# CY7USB3014.net
KiCad netlist of a schematic drawn in Altium Designer
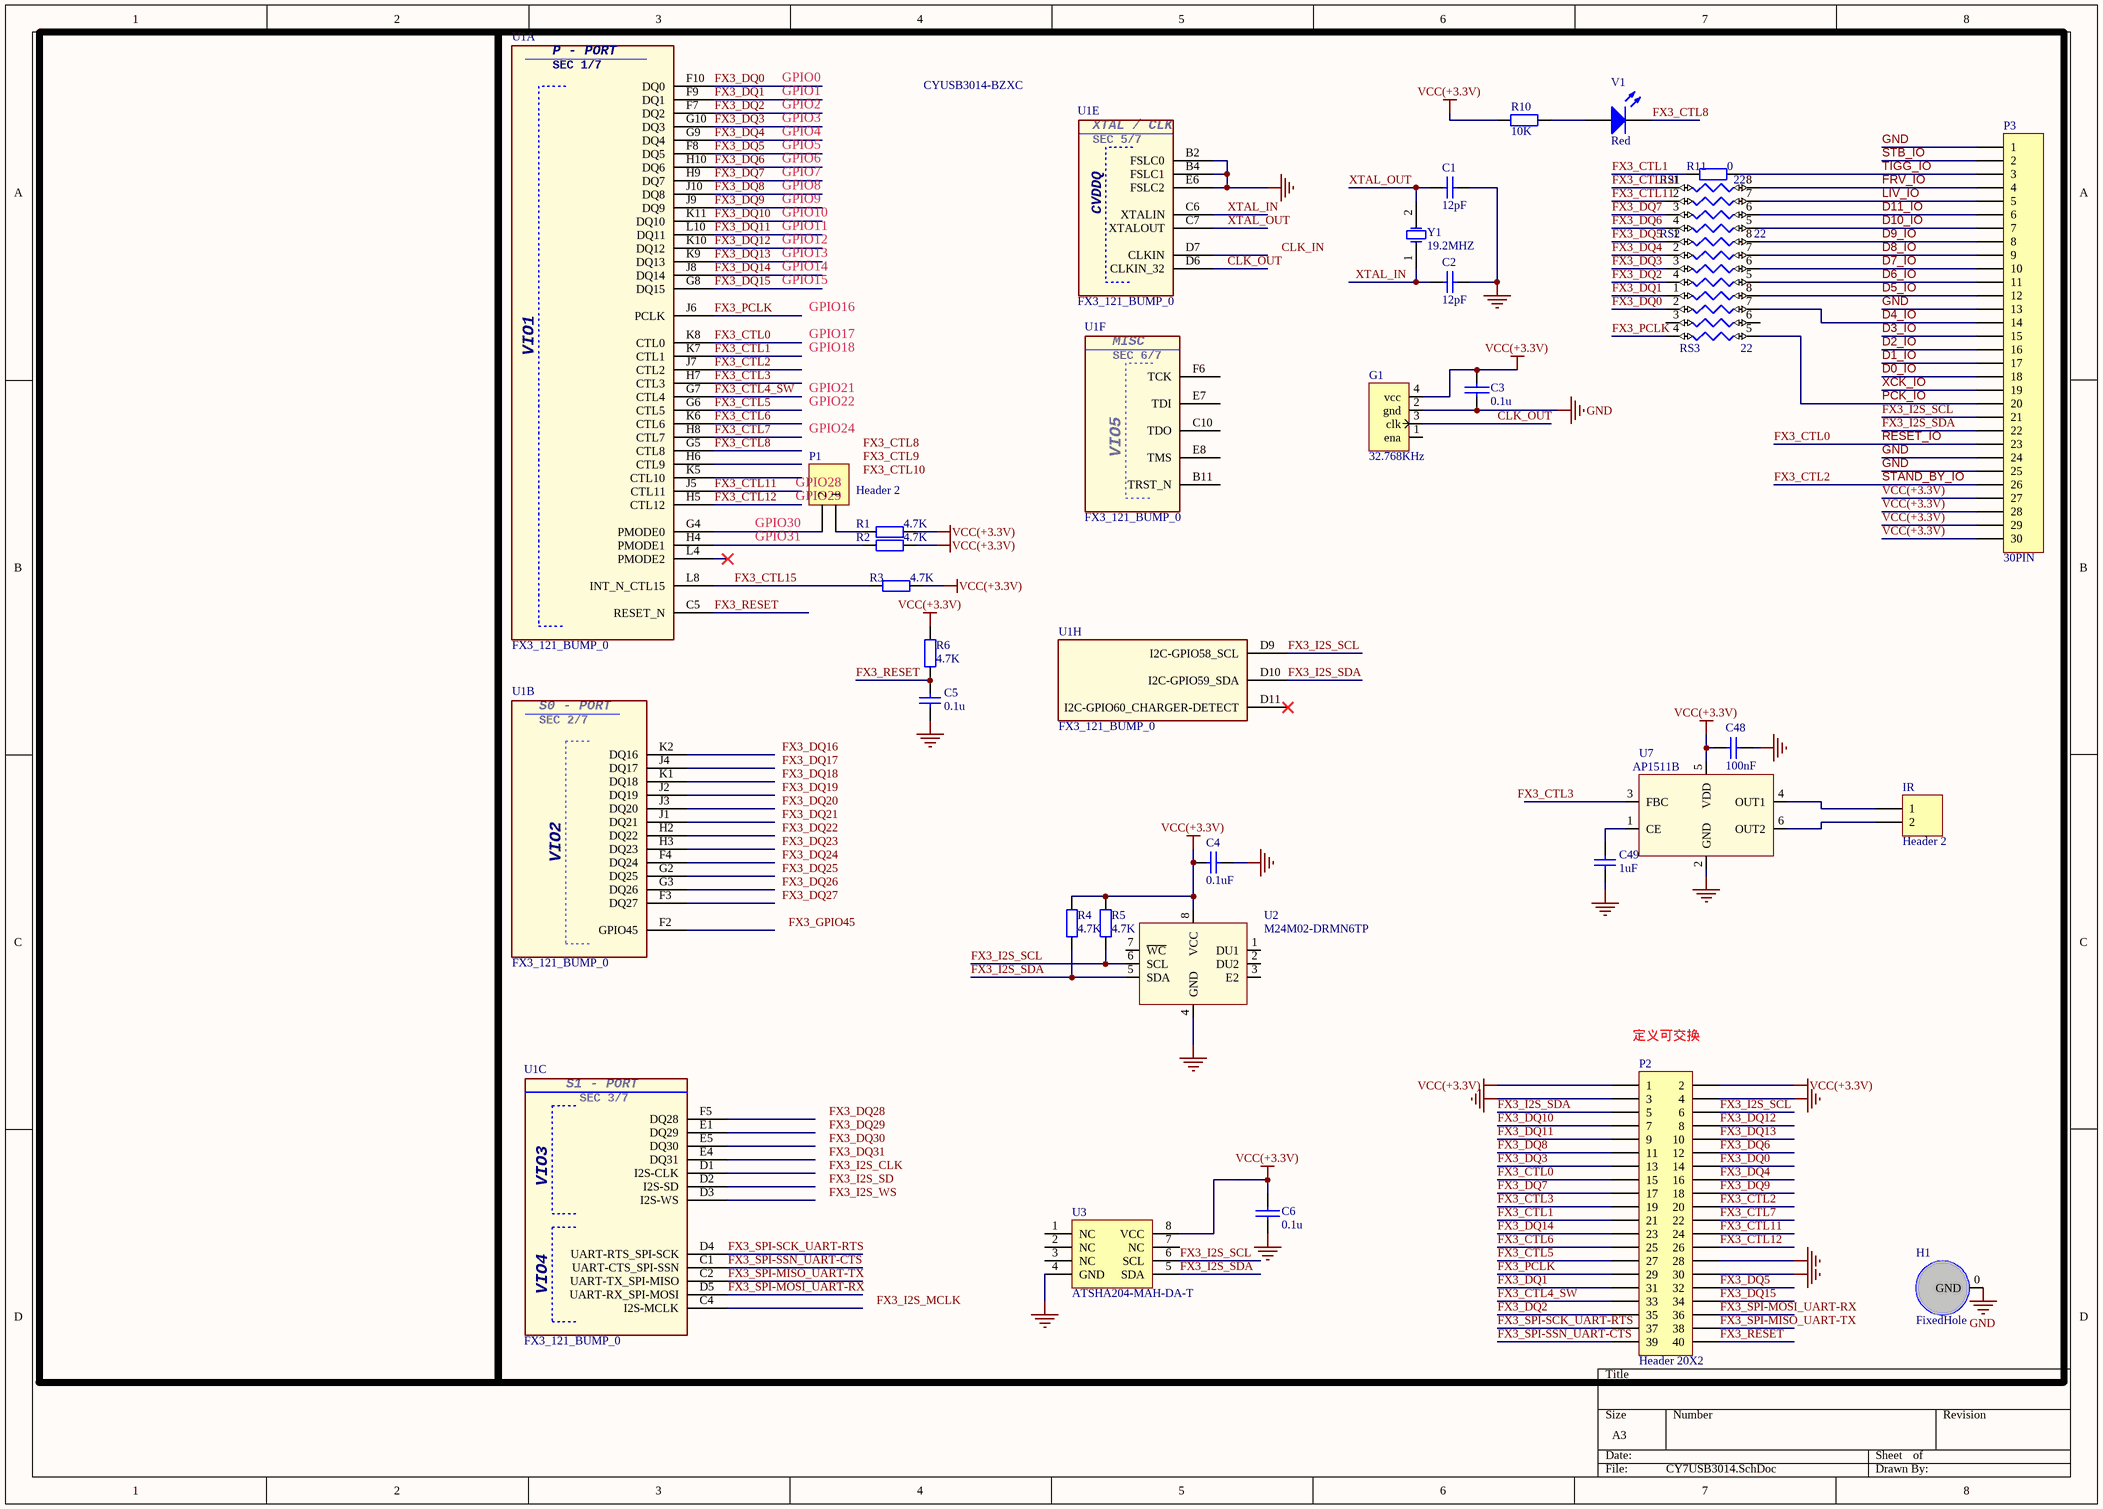
[diagram p0: CY7USB3014.SchDoc]

(export (version "E")
  (design (tool "Eeschema 10.0.6"))
  (components
    (comp (ref "C1")
      (value "12pF")
      (footprint "0603S-CAP")
      (description "CAP CER SMT 4.3pF 0805")
      (fields
        (field (name "2. MANUFACTURERE PART NUMBER") "C0805C439D5GACTU")
        (field (name "8. ALTERNATE PART") "any")
      )
      (libsource (lib "Peeple_eval") (part "CAP CER SMT 4.3pF 0805"))
    )
    (comp (ref "C2")
      (value "12pF")
      (footprint "0603S-CAP")
      (description "CAP CER SMT 4.3pF 0805")
      (fields
        (field (name "2. MANUFACTURERE PART NUMBER") "C0805C439D5GACTU")
        (field (name "8. ALTERNATE PART") "any")
      )
      (libsource (lib "Peeple_eval") (part "CAP CER SMT 4.3pF 0805"))
    )
    (comp (ref "C3")
      (value "0.1u")
      (footprint "0603S-CAP")
      (description "RC=1206")
      (libsource (lib "*") (part "CAP"))
    )
    (comp (ref "C4")
      (value "0.1uF")
      (footprint "0603S-CAP")
      (description "CAP SMT 0.1uF 16V X7R")
      (fields
        (field (name "2. MANUFACTURERE PART NUMBER") "C0805C104K4RACTU")
        (field (name "8. ALTERNATE PART") "any")
      )
      (libsource (lib "Peeple_eval") (part "CAP SMT 0.1uF 16V X7R"))
    )
    (comp (ref "C5")
      (value "0.1u")
      (footprint "0603S-CAP")
      (description "50V/8.2u/0805")
      (fields (field (name "PUBLISHER") "Altium Limited"))
      (libsource (lib "Miscellaneous Devices") (part "Cap"))
    )
    (comp (ref "C6")
      (value "0.1u")
      (footprint "0603S-CAP")
      (description "RC=1206")
      (libsource (lib "*") (part "CAP"))
    )
    (comp (ref "C48")
      (value "100nF")
      (footprint "0603S-CAP")
      (description "50V/8.2u/0805")
      (fields (field (name "PUBLISHER") "Altium Limited"))
      (libsource (lib "Miscellaneous Devices") (part "Cap"))
    )
    (comp (ref "C49")
      (value "1uF")
      (footprint "0603S-CAP")
      (description "50V/8.2u/0805")
      (fields (field (name "PUBLISHER") "Altium Limited"))
      (libsource (lib "Miscellaneous Devices") (part "Cap"))
    )
    (comp (ref "G1") (value "32.768KHz") (footprint "爱普生晶振3.2×2.5mm") (libsource (lib "*") (part "CTY4-B")))
    (comp (ref "H1") (value "FixedHole") (footprint "固定孔_1") (libsource (lib "ITMS-02调试电缆转接板") (part "固定孔")))
    (comp (ref "IR")
      (value "Header 2")
      (footprint "1.25mm")
      (description "Header, 2-Pin")
      (fields (field (name "PUBLISHER") "Altium Limited"))
      (libsource (lib "Miscellaneous Connectors") (part "Header 2"))
    )
    (comp (ref "P1")
      (value "Header 2")
      (footprint "HDR1X2")
      (description "Header, 2-Pin")
      (fields (field (name "PUBLISHER") "Altium Limited"))
      (libsource (lib "") (part "Header 2_1"))
    )
    (comp (ref "P2")
      (value "Header 20X2")
      (footprint "1.27mm 2*20")
      (description "Header, 20-Pin, Dual row")
      (fields (field (name "PUBLISHER") "Altium Limited"))
      (libsource (lib "Miscellaneous Connectors") (part "Header 20X2"))
    )
    (comp (ref "P3")
      (value "30PIN")
      (footprint "FH12-30S-0.5SH")
      (description "Header, 30-Pin")
      (fields (field (name "PUBLISHER") "Altium Limited"))
      (libsource (lib "Miscellaneous Connectors") (part "Header 30"))
    )
    (comp (ref "R1")
      (value "4.7K")
      (footprint "0603S-RES")
      (description "Resistor")
      (fields (field (name "PUBLISHER") "Altium Limited"))
      (libsource (lib "DM642") (part "Res2"))
    )
    (comp (ref "R2")
      (value "4.7K")
      (footprint "0603S-RES")
      (description "Resistor")
      (fields (field (name "PUBLISHER") "Altium Limited"))
      (libsource (lib "DM642") (part "Res2"))
    )
    (comp (ref "R3")
      (value "4.7K")
      (footprint "0603S-RES")
      (description "Resistor")
      (fields (field (name "PUBLISHER") "Altium Limited"))
      (libsource (lib "") (part "Res2_2"))
    )
    (comp (ref "R4")
      (value "4.7K")
      (footprint "0603S-RES")
      (description "Resistor")
      (fields (field (name "PUBLISHER") "Altium Limited"))
      (libsource (lib "DM642") (part "Res2"))
    )
    (comp (ref "R5")
      (value "4.7K")
      (footprint "0603S-RES")
      (description "Resistor")
      (fields (field (name "PUBLISHER") "Altium Limited"))
      (libsource (lib "DM642") (part "Res2"))
    )
    (comp (ref "R6")
      (value "4.7K")
      (footprint "0603S-RES")
      (description "Resistor")
      (fields (field (name "PUBLISHER") "Altium Limited"))
      (libsource (lib "") (part "Res2_3"))
    )
    (comp (ref "R10")
      (value "10K")
      (footprint "0603S-RES")
      (description "Resistor")
      (fields (field (name "PUBLISHER") "Altium Limited"))
      (libsource (lib "") (part "Res2_1"))
    )
    (comp (ref "R11")
      (value "0")
      (footprint "0603S-RES")
      (description "Resistor")
      (fields (field (name "PUBLISHER") "Altium Limited"))
      (libsource (lib "") (part "Res2_1"))
    )
    (comp (ref "RS1") (value "22") (footprint "NC06-4") (libsource (lib "*") (part "RN4")))
    (comp (ref "RS2") (value "22") (footprint "NC06-4") (libsource (lib "*") (part "RN4")))
    (comp (ref "RS3") (value "22") (footprint "NC06-4") (libsource (lib "*") (part "RN4")))
    (comp (ref "U1")
      (value "FX3_121_BUMP_0")
      (footprint "121_BGA_FX3")
      (libsource (lib "USB_CAMERA") (part "FX3_121_BUMP_0"))
    )
    (comp (ref "U2")
      (value "M24M02-DRMN6TP")
      (footprint "SOIC127P600X175-8N")
      (description "IC EEPROM 64KBIT 400KHZ 8SOIC")
      (fields
        (field (name "MANUFACTURER") "Microchip Technology")
        (field (name "MANUFACTURER PART NUMBER") "24LC64-I/SN")
      )
      (libsource (lib "Schlib1") (part "24LC64-I/SN"))
    )
    (comp (ref "U3")
      (value "ATSHA204-MAH-DA-T")
      (footprint "UDFN")
      (libsource (lib "CY7C68013-56") (part "AT24C128"))
    )
    (comp (ref "U7") (value "AP1511B") (footprint "SOT-26") (libsource (lib "noir") (part "AP1511B")))
    (comp (ref "V1")
      (value "Red")
      (footprint "LED0805S")
      (description "Typical INFRARED GaAs LED")
      (fields (field (name "PUBLISHER") "Altium Limited"))
      (libsource (lib "DM642") (part "LED0"))
    )
    (comp (ref "Y1")
      (value "19.2MHZ")
      (footprint "爱普生晶振3.2×2.5MM - 无源")
      (description "Crystal, CRYSTAL 32.768KHZ 6PF SMD")
      (fields
        (field (name "2. MANUFACTURERE PART NUMBER") "ABS07-120-32.768KHZ-T")
        (field (name "4. SUPPLIER PART NUMBER") "535-11937-1-ND")
      )
      (libsource (lib "Peeple_eval") (part "XTAL 32.768KHZ"))
    )
  )
  (nets
    (net (code "2") (name "/CLK_OUT") (class "Default")
      (node (ref "G1") (pin "3") (pinfunction "clk_3") (pintype "passive"))
      (node (ref "U1") (pin "D6") (pinfunction "CLKIN_32_D6") (pintype "passive"))
    )
    (net (code "3") (name "/D0_IO") (class "Default")
      (node (ref "P3") (pin "18") (pinfunction "18_18") (pintype "passive"))
    )
    (net (code "4") (name "/D1_IO") (class "Default")
      (node (ref "P3") (pin "17") (pinfunction "17_17") (pintype "passive"))
    )
    (net (code "5") (name "/D2_IO") (class "Default")
      (node (ref "P3") (pin "16") (pinfunction "16_16") (pintype "passive"))
    )
    (net (code "6") (name "/D3_IO") (class "Default")
      (node (ref "P3") (pin "15") (pinfunction "15_15") (pintype "passive"))
    )
    (net (code "7") (name "/D4_IO") (class "Default")
      (node (ref "P3") (pin "14") (pinfunction "14_14") (pintype "passive"))
      (node (ref "RS3") (pin "7") (pinfunction "7_7") (pintype "bidirectional"))
    )
    (net (code "8") (name "/D5_IO") (class "Default")
      (node (ref "P3") (pin "12") (pinfunction "12_12") (pintype "passive"))
      (node (ref "RS3") (pin "8") (pinfunction "8_8") (pintype "bidirectional"))
    )
    (net (code "9") (name "/D6_IO") (class "Default")
      (node (ref "P3") (pin "11") (pinfunction "11_11") (pintype "passive"))
      (node (ref "RS2") (pin "5") (pinfunction "5_5") (pintype "bidirectional"))
    )
    (net (code "10") (name "/D7_IO") (class "Default")
      (node (ref "P3") (pin "10") (pinfunction "10_10") (pintype "passive"))
      (node (ref "RS2") (pin "6") (pinfunction "6_6") (pintype "bidirectional"))
    )
    (net (code "11") (name "/D8_IO") (class "Default")
      (node (ref "P3") (pin "9") (pinfunction "9_9") (pintype "passive"))
      (node (ref "RS2") (pin "7") (pinfunction "7_7") (pintype "bidirectional"))
    )
    (net (code "12") (name "/D9_IO") (class "Default")
      (node (ref "P3") (pin "8") (pinfunction "8_8") (pintype "passive"))
      (node (ref "RS2") (pin "8") (pinfunction "8_8") (pintype "bidirectional"))
    )
    (net (code "13") (name "/D10_IO") (class "Default")
      (node (ref "P3") (pin "7") (pinfunction "7_7") (pintype "passive"))
      (node (ref "RS1") (pin "5") (pinfunction "5_5") (pintype "bidirectional"))
    )
    (net (code "14") (name "/D11_IO") (class "Default")
      (node (ref "P3") (pin "6") (pinfunction "6_6") (pintype "passive"))
      (node (ref "RS1") (pin "6") (pinfunction "6_6") (pintype "bidirectional"))
    )
    (net (code "15") (name "/FRV_IO") (class "Default")
      (node (ref "P3") (pin "4") (pinfunction "4_4") (pintype "passive"))
      (node (ref "RS1") (pin "8") (pinfunction "8_8") (pintype "bidirectional"))
    )
    (net (code "16") (name "/FX3_CTL0") (class "Default")
      (node (ref "P2") (pin "15") (pinfunction "15_15") (pintype "passive"))
      (node (ref "P3") (pin "23") (pinfunction "23_23") (pintype "passive"))
      (node (ref "U1") (pin "K8") (pinfunction "CTL0_K8") (pintype "passive"))
    )
    (net (code "17") (name "/FX3_CTL1") (class "Default")
      (node (ref "P2") (pin "21") (pinfunction "21_21") (pintype "passive"))
      (node (ref "R11") (pin "2") (pinfunction "2_2") (pintype "passive"))
      (node (ref "U1") (pin "K7") (pinfunction "CTL1_K7") (pintype "passive"))
    )
    (net (code "18") (name "/FX3_CTL2") (class "Default")
      (node (ref "P2") (pin "20") (pinfunction "20_20") (pintype "passive"))
      (node (ref "P3") (pin "26") (pinfunction "26_26") (pintype "passive"))
      (node (ref "U1") (pin "J7") (pinfunction "CTL2_J7") (pintype "passive"))
    )
    (net (code "19") (name "/FX3_CTL3") (class "Default")
      (node (ref "P2") (pin "19") (pinfunction "19_19") (pintype "passive"))
      (node (ref "U1") (pin "H7") (pinfunction "CTL3_H7") (pintype "passive"))
    )
    (net (code "20") (name "/FX3_CTL4_SW") (class "Default")
      (node (ref "P2") (pin "33") (pinfunction "33_33") (pintype "passive"))
      (node (ref "U1") (pin "G7") (pinfunction "CTL4_G7") (pintype "passive"))
    )
    (net (code "21") (name "/FX3_CTL5") (class "Default")
      (node (ref "P2") (pin "27") (pinfunction "27_27") (pintype "passive"))
      (node (ref "U1") (pin "G6") (pinfunction "CTL5_G6") (pintype "passive"))
    )
    (net (code "22") (name "/FX3_CTL6") (class "Default")
      (node (ref "P2") (pin "25") (pinfunction "25_25") (pintype "passive"))
      (node (ref "U1") (pin "K6") (pinfunction "CTL6_K6") (pintype "passive"))
    )
    (net (code "23") (name "/FX3_CTL7") (class "Default")
      (node (ref "P2") (pin "22") (pinfunction "22_22") (pintype "passive"))
      (node (ref "U1") (pin "H8") (pinfunction "CTL7_H8") (pintype "passive"))
    )
    (net (code "24") (name "/FX3_CTL8") (class "Default")
      (node (ref "U1") (pin "G5") (pinfunction "CTL8_G5") (pintype "passive"))
      (node (ref "V1") (pin "2") (pinfunction "K_2") (pintype "passive"))
    )
    (net (code "27") (name "/FX3_CTL11") (class "Default")
      (node (ref "P2") (pin "24") (pinfunction "24_24") (pintype "passive"))
      (node (ref "RS1") (pin "2") (pinfunction "2_2") (pintype "bidirectional"))
      (node (ref "U1") (pin "J5") (pinfunction "CTL11_J5") (pintype "passive"))
    )
    (net (code "28") (name "/FX3_CTL12") (class "Default")
      (node (ref "P2") (pin "26") (pinfunction "26_26") (pintype "passive"))
      (node (ref "RS1") (pin "1") (pinfunction "1_1") (pintype "bidirectional"))
      (node (ref "U1") (pin "H5") (pinfunction "CTL12_H5") (pintype "passive"))
    )
    (net (code "29") (name "/FX3_CTL15") (class "Default")
      (node (ref "R3") (pin "2") (pinfunction "2_2") (pintype "passive"))
      (node (ref "U1") (pin "L8") (pinfunction "INT_N_CTL15_L8") (pintype "passive"))
    )
    (net (code "30") (name "/FX3_DQ0") (class "Default")
      (node (ref "P2") (pin "14") (pinfunction "14_14") (pintype "passive"))
      (node (ref "RS3") (pin "2") (pinfunction "2_2") (pintype "bidirectional"))
      (node (ref "U1") (pin "F10") (pinfunction "DQ0_F10") (pintype "passive"))
    )
    (net (code "31") (name "/FX3_DQ1") (class "Default")
      (node (ref "P2") (pin "31") (pinfunction "31_31") (pintype "passive"))
      (node (ref "RS3") (pin "1") (pinfunction "1_1") (pintype "bidirectional"))
      (node (ref "U1") (pin "F9") (pinfunction "DQ1_F9") (pintype "passive"))
    )
    (net (code "32") (name "/FX3_DQ2") (class "Default")
      (node (ref "P2") (pin "35") (pinfunction "35_35") (pintype "passive"))
      (node (ref "RS2") (pin "4") (pinfunction "4_4") (pintype "bidirectional"))
      (node (ref "U1") (pin "F7") (pinfunction "DQ2_F7") (pintype "passive"))
    )
    (net (code "33") (name "/FX3_DQ3") (class "Default")
      (node (ref "P2") (pin "13") (pinfunction "13_13") (pintype "passive"))
      (node (ref "RS2") (pin "3") (pinfunction "3_3") (pintype "bidirectional"))
      (node (ref "U1") (pin "G10") (pinfunction "DQ3_G10") (pintype "passive"))
    )
    (net (code "34") (name "/FX3_DQ4") (class "Default")
      (node (ref "P2") (pin "16") (pinfunction "16_16") (pintype "passive"))
      (node (ref "RS2") (pin "2") (pinfunction "2_2") (pintype "bidirectional"))
      (node (ref "U1") (pin "G9") (pinfunction "DQ4_G9") (pintype "passive"))
    )
    (net (code "35") (name "/FX3_DQ5") (class "Default")
      (node (ref "P2") (pin "32") (pinfunction "32_32") (pintype "passive"))
      (node (ref "RS2") (pin "1") (pinfunction "1_1") (pintype "bidirectional"))
      (node (ref "U1") (pin "F8") (pinfunction "DQ5_F8") (pintype "passive"))
    )
    (net (code "36") (name "/FX3_DQ6") (class "Default")
      (node (ref "P2") (pin "12") (pinfunction "12_12") (pintype "passive"))
      (node (ref "RS1") (pin "4") (pinfunction "4_4") (pintype "bidirectional"))
      (node (ref "U1") (pin "H10") (pinfunction "DQ6_H10") (pintype "passive"))
    )
    (net (code "37") (name "/FX3_DQ7") (class "Default")
      (node (ref "P2") (pin "17") (pinfunction "17_17") (pintype "passive"))
      (node (ref "RS1") (pin "3") (pinfunction "3_3") (pintype "bidirectional"))
      (node (ref "U1") (pin "H9") (pinfunction "DQ7_H9") (pintype "passive"))
    )
    (net (code "38") (name "/FX3_DQ8") (class "Default")
      (node (ref "P2") (pin "11") (pinfunction "11_11") (pintype "passive"))
      (node (ref "U1") (pin "J10") (pinfunction "DQ8_J10") (pintype "passive"))
    )
    (net (code "39") (name "/FX3_DQ9") (class "Default")
      (node (ref "P2") (pin "18") (pinfunction "18_18") (pintype "passive"))
      (node (ref "U1") (pin "J9") (pinfunction "DQ9_J9") (pintype "passive"))
    )
    (net (code "40") (name "/FX3_DQ10") (class "Default")
      (node (ref "P2") (pin "7") (pinfunction "7_7") (pintype "passive"))
      (node (ref "U1") (pin "K11") (pinfunction "DQ10_K11") (pintype "passive"))
    )
    (net (code "41") (name "/FX3_DQ11") (class "Default")
      (node (ref "P2") (pin "9") (pinfunction "9_9") (pintype "passive"))
      (node (ref "U1") (pin "L10") (pinfunction "DQ11_L10") (pintype "passive"))
    )
    (net (code "42") (name "/FX3_DQ12") (class "Default")
      (node (ref "P2") (pin "8") (pinfunction "8_8") (pintype "passive"))
      (node (ref "U1") (pin "K10") (pinfunction "DQ12_K10") (pintype "passive"))
    )
    (net (code "43") (name "/FX3_DQ13") (class "Default")
      (node (ref "P2") (pin "10") (pinfunction "10_10") (pintype "passive"))
      (node (ref "U1") (pin "K9") (pinfunction "DQ13_K9") (pintype "passive"))
    )
    (net (code "44") (name "/FX3_DQ14") (class "Default")
      (node (ref "P2") (pin "23") (pinfunction "23_23") (pintype "passive"))
      (node (ref "U1") (pin "J8") (pinfunction "DQ14_J8") (pintype "passive"))
    )
    (net (code "45") (name "/FX3_DQ15") (class "Default")
      (node (ref "P2") (pin "34") (pinfunction "34_34") (pintype "passive"))
      (node (ref "U1") (pin "G8") (pinfunction "DQ15_G8") (pintype "passive"))
    )
    (net (code "65") (name "/FX3_I2S_SCL") (class "Default")
      (node (ref "P2") (pin "6") (pinfunction "6_6") (pintype "passive"))
      (node (ref "P3") (pin "21") (pinfunction "21_21") (pintype "passive"))
      (node (ref "R5") (pin "1") (pinfunction "1_1") (pintype "passive"))
      (node (ref "U1") (pin "D9") (pinfunction "I2C-GPIO58_SCL_D9") (pintype "passive"))
      (node (ref "U2") (pin "6") (pinfunction "SCL_6") (pintype "passive"))
      (node (ref "U3") (pin "6") (pinfunction "SCL_6") (pintype "passive"))
    )
    (net (code "67") (name "/FX3_I2S_SDA") (class "Default")
      (node (ref "P2") (pin "5") (pinfunction "5_5") (pintype "passive"))
      (node (ref "P3") (pin "22") (pinfunction "22_22") (pintype "passive"))
      (node (ref "R4") (pin "1") (pinfunction "1_1") (pintype "passive"))
      (node (ref "U1") (pin "D10") (pinfunction "I2C-GPIO59_SDA_D10") (pintype "passive"))
      (node (ref "U2") (pin "5") (pinfunction "SDA_5") (pintype "passive"))
      (node (ref "U3") (pin "5") (pinfunction "SDA_5") (pintype "passive"))
    )
    (net (code "69") (name "/FX3_PCLK") (class "Default")
      (node (ref "P2") (pin "29") (pinfunction "29_29") (pintype "passive"))
      (node (ref "RS3") (pin "4") (pinfunction "4_4") (pintype "bidirectional"))
      (node (ref "U1") (pin "J6") (pinfunction "PCLK_J6") (pintype "passive"))
    )
    (net (code "70") (name "/FX3_RESET") (class "Default")
      (node (ref "C5") (pin "2") (pinfunction "2_2") (pintype "passive"))
      (node (ref "P2") (pin "40") (pinfunction "40_40") (pintype "passive"))
      (node (ref "R6") (pin "2") (pinfunction "2_2") (pintype "passive"))
      (node (ref "U1") (pin "C5") (pinfunction "RESET_N_C5") (pintype "passive"))
    )
    (net (code "71") (name "/FX3_SPI-MISO_UART-TX") (class "Default")
      (node (ref "P2") (pin "38") (pinfunction "38_38") (pintype "passive"))
      (node (ref "U1") (pin "C2") (pinfunction "UART-TX_SPI-MISO_C2") (pintype "passive"))
    )
    (net (code "72") (name "/FX3_SPI-MOSI_UART-RX") (class "Default")
      (node (ref "P2") (pin "36") (pinfunction "36_36") (pintype "passive"))
      (node (ref "U1") (pin "D5") (pinfunction "UART-RX_SPI-MOSI_D5") (pintype "passive"))
    )
    (net (code "73") (name "/FX3_SPI-SCK_UART-RTS") (class "Default")
      (node (ref "P2") (pin "37") (pinfunction "37_37") (pintype "passive"))
      (node (ref "U1") (pin "D4") (pinfunction "UART-RTS_SPI-SCK_D4") (pintype "passive"))
    )
    (net (code "74") (name "/FX3_SPI-SSN_UART-CTS") (class "Default")
      (node (ref "P2") (pin "39") (pinfunction "39_39") (pintype "passive"))
      (node (ref "U1") (pin "C1") (pinfunction "UART-CTS_SPI-SSN_C1") (pintype "passive"))
    )
    (net (code "75") (name "/LIV_IO") (class "Default")
      (node (ref "P3") (pin "5") (pinfunction "5_5") (pintype "passive"))
      (node (ref "RS1") (pin "7") (pinfunction "7_7") (pintype "bidirectional"))
    )
    (net (code "76") (name "/PCK_IO") (class "Default")
      (node (ref "P3") (pin "20") (pinfunction "20_20") (pintype "passive"))
      (node (ref "RS3") (pin "5") (pinfunction "5_5") (pintype "bidirectional"))
    )
    (net (code "77") (name "/STB_IO") (class "Default")
      (node (ref "P3") (pin "2") (pinfunction "2_2") (pintype "passive"))
    )
    (net (code "78") (name "/TIGG_IO") (class "Default")
      (node (ref "P3") (pin "3") (pinfunction "3_3") (pintype "passive"))
      (node (ref "R11") (pin "1") (pinfunction "1_1") (pintype "passive"))
    )
    (net (code "79") (name "/XCK_IO") (class "Default")
      (node (ref "P3") (pin "19") (pinfunction "19_19") (pintype "passive"))
    )
    (net (code "80") (name "/XTAL_IN") (class "Default")
      (node (ref "C2") (pin "2") (pinfunction "2_2") (pintype "passive"))
      (node (ref "U1") (pin "C6") (pinfunction "XTALIN_C6") (pintype "passive"))
      (node (ref "Y1") (pin "1") (pinfunction "OSC1_1") (pintype "passive"))
    )
    (net (code "81") (name "/XTAL_OUT") (class "Default")
      (node (ref "C1") (pin "2") (pinfunction "2_2") (pintype "passive"))
      (node (ref "U1") (pin "C7") (pinfunction "XTALOUT_C7") (pintype "passive"))
      (node (ref "Y1") (pin "2") (pinfunction "OSC2_2") (pintype "passive"))
    )
    (net (code "82") (name "GND") (class "Default")
      (node (ref "C1") (pin "1") (pinfunction "1_1") (pintype "passive"))
      (node (ref "C2") (pin "1") (pinfunction "1_1") (pintype "passive"))
      (node (ref "C3") (pin "2") (pintype "passive"))
      (node (ref "C4") (pin "1") (pinfunction "1_1") (pintype "passive"))
      (node (ref "C48") (pin "1") (pinfunction "1_1") (pintype "passive"))
      (node (ref "C49") (pin "1") (pinfunction "1_1") (pintype "passive"))
      (node (ref "C5") (pin "1") (pinfunction "1_1") (pintype "passive"))
      (node (ref "C6") (pin "2") (pintype "passive"))
      (node (ref "G1") (pin "2") (pinfunction "gnd_2") (pintype "power_in"))
      (node (ref "H1") (pin "0") (pinfunction "GND_0") (pintype "passive"))
      (node (ref "P2") (pin "28") (pinfunction "28_28") (pintype "passive"))
      (node (ref "P2") (pin "3") (pinfunction "3_3") (pintype "passive"))
      (node (ref "P2") (pin "30") (pinfunction "30_30") (pintype "passive"))
      (node (ref "P2") (pin "4") (pinfunction "4_4") (pintype "passive"))
      (node (ref "P3") (pin "1") (pinfunction "1_1") (pintype "passive"))
      (node (ref "P3") (pin "13") (pinfunction "13_13") (pintype "passive"))
      (node (ref "P3") (pin "24") (pinfunction "24_24") (pintype "passive"))
      (node (ref "P3") (pin "25") (pinfunction "25_25") (pintype "passive"))
      (node (ref "U1") (pin "B2") (pinfunction "FSLC0_B2") (pintype "passive"))
      (node (ref "U1") (pin "B4") (pinfunction "FSLC1_B4") (pintype "passive"))
      (node (ref "U1") (pin "E6") (pinfunction "FSLC2_E6") (pintype "passive"))
      (node (ref "U2") (pin "4") (pinfunction "GND_4") (pintype "passive"))
      (node (ref "U3") (pin "4") (pinfunction "GND_4") (pintype "passive"))
      (node (ref "U7") (pin "2") (pinfunction "GND_2") (pintype "passive"))
    )
    (net (code "83") (name "Net-(P1-Pad1)") (class "Default")
      (node (ref "P1") (pin "1") (pinfunction "1_1") (pintype "passive"))
      (node (ref "R1") (pin "1") (pinfunction "1_1") (pintype "passive"))
    )
    (net (code "84") (name "Net-(U1A-PMODE0)") (class "Default")
      (node (ref "P1") (pin "2") (pinfunction "2_2") (pintype "passive"))
      (node (ref "U1") (pin "G4") (pinfunction "PMODE0_G4") (pintype "passive"))
    )
    (net (code "85") (name "Net-(U1A-PMODE1)") (class "Default")
      (node (ref "R2") (pin "1") (pinfunction "1_1") (pintype "passive"))
      (node (ref "U1") (pin "H4") (pinfunction "PMODE1_H4") (pintype "passive"))
    )
    (net (code "86") (name "Net-(U7-CE)") (class "Default")
      (node (ref "C49") (pin "2") (pinfunction "2_2") (pintype "passive"))
      (node (ref "U7") (pin "1") (pinfunction "CE_1") (pintype "passive"))
    )
    (net (code "87") (name "Net-(U7-OUT1)") (class "Default")
      (node (ref "IR") (pin "1") (pinfunction "1_1") (pintype "passive"))
      (node (ref "U7") (pin "4") (pinfunction "OUT1_4") (pintype "passive"))
    )
    (net (code "88") (name "Net-(U7-OUT2)") (class "Default")
      (node (ref "IR") (pin "2") (pinfunction "2_2") (pintype "passive"))
      (node (ref "U7") (pin "6") (pinfunction "OUT2_6") (pintype "passive"))
    )
    (net (code "89") (name "Net-(V1-A)") (class "Default")
      (node (ref "R10") (pin "1") (pinfunction "1_1") (pintype "passive"))
      (node (ref "V1") (pin "1") (pinfunction "A_1") (pintype "passive"))
    )
    (net (code "90") (name "VCC(+3.3V)") (class "Default")
      (node (ref "C3") (pin "1") (pintype "passive"))
      (node (ref "C4") (pin "2") (pinfunction "2_2") (pintype "passive"))
      (node (ref "C48") (pin "2") (pinfunction "2_2") (pintype "passive"))
      (node (ref "C6") (pin "1") (pintype "passive"))
      (node (ref "G1") (pin "4") (pinfunction "vcc_4") (pintype "power_in"))
      (node (ref "P2") (pin "1") (pinfunction "1_1") (pintype "passive"))
      (node (ref "P2") (pin "2") (pinfunction "2_2") (pintype "passive"))
      (node (ref "P3") (pin "27") (pinfunction "27_27") (pintype "passive"))
      (node (ref "P3") (pin "28") (pinfunction "28_28") (pintype "passive"))
      (node (ref "P3") (pin "29") (pinfunction "29_29") (pintype "passive"))
      (node (ref "P3") (pin "30") (pinfunction "30_30") (pintype "passive"))
      (node (ref "R1") (pin "2") (pinfunction "2_2") (pintype "passive"))
      (node (ref "R10") (pin "2") (pinfunction "2_2") (pintype "passive"))
      (node (ref "R2") (pin "2") (pinfunction "2_2") (pintype "passive"))
      (node (ref "R3") (pin "1") (pinfunction "1_1") (pintype "passive"))
      (node (ref "R4") (pin "2") (pinfunction "2_2") (pintype "passive"))
      (node (ref "R5") (pin "2") (pinfunction "2_2") (pintype "passive"))
      (node (ref "R6") (pin "1") (pinfunction "1_1") (pintype "passive"))
      (node (ref "U2") (pin "8") (pinfunction "VCC_8") (pintype "passive"))
      (node (ref "U3") (pin "8") (pinfunction "VCC_8") (pintype "passive"))
      (node (ref "U7") (pin "5") (pinfunction "VDD_5") (pintype "passive"))
    )
    (net (code "91") (name "unconnected-(G1-ena-Pad1)") (class "Default")
      (node (ref "G1") (pin "1") (pinfunction "ena_1") (pintype "passive"))
    )
    (net (code "92") (name "unconnected-(RS3-Pad3)") (class "Default")
      (node (ref "RS3") (pin "3") (pinfunction "3_3") (pintype "bidirectional"))
    )
    (net (code "93") (name "unconnected-(RS3-Pad6)") (class "Default")
      (node (ref "RS3") (pin "6") (pinfunction "6_6") (pintype "bidirectional"))
    )
    (net (code "94") (name "unconnected-(U1A-CTL9-PadH6)") (class "Default")
      (node (ref "U1") (pin "H6") (pinfunction "CTL9_H6") (pintype "passive"))
    )
    (net (code "95") (name "unconnected-(U1A-CTL10-PadK5)") (class "Default")
      (node (ref "U1") (pin "K5") (pinfunction "CTL10_K5") (pintype "passive"))
    )
    (net (code "96") (name "unconnected-(U1A-PMODE2-PadL4)") (class "Default")
      (node (ref "U1") (pin "L4") (pinfunction "PMODE2_L4") (pintype "passive+no_connect"))
    )
    (net (code "97") (name "unconnected-(U1B-DQ16-PadK2)") (class "Default")
      (node (ref "U1") (pin "K2") (pinfunction "DQ16_K2") (pintype "passive"))
    )
    (net (code "98") (name "unconnected-(U1B-DQ17-PadJ4)") (class "Default")
      (node (ref "U1") (pin "J4") (pinfunction "DQ17_J4") (pintype "passive"))
    )
    (net (code "99") (name "unconnected-(U1B-DQ18-PadK1)") (class "Default")
      (node (ref "U1") (pin "K1") (pinfunction "DQ18_K1") (pintype "passive"))
    )
    (net (code "100") (name "unconnected-(U1B-DQ19-PadJ2)") (class "Default")
      (node (ref "U1") (pin "J2") (pinfunction "DQ19_J2") (pintype "passive"))
    )
    (net (code "101") (name "unconnected-(U1B-DQ20-PadJ3)") (class "Default")
      (node (ref "U1") (pin "J3") (pinfunction "DQ20_J3") (pintype "passive"))
    )
    (net (code "102") (name "unconnected-(U1B-DQ21-PadJ1)") (class "Default")
      (node (ref "U1") (pin "J1") (pinfunction "DQ21_J1") (pintype "passive"))
    )
    (net (code "103") (name "unconnected-(U1B-DQ22-PadH2)") (class "Default")
      (node (ref "U1") (pin "H2") (pinfunction "DQ22_H2") (pintype "passive"))
    )
    (net (code "104") (name "unconnected-(U1B-DQ23-PadH3)") (class "Default")
      (node (ref "U1") (pin "H3") (pinfunction "DQ23_H3") (pintype "passive"))
    )
    (net (code "105") (name "unconnected-(U1B-DQ24-PadF4)") (class "Default")
      (node (ref "U1") (pin "F4") (pinfunction "DQ24_F4") (pintype "passive"))
    )
    (net (code "106") (name "unconnected-(U1B-DQ25-PadG2)") (class "Default")
      (node (ref "U1") (pin "G2") (pinfunction "DQ25_G2") (pintype "passive"))
    )
    (net (code "107") (name "unconnected-(U1B-DQ26-PadG3)") (class "Default")
      (node (ref "U1") (pin "G3") (pinfunction "DQ26_G3") (pintype "passive"))
    )
    (net (code "108") (name "unconnected-(U1B-DQ27-PadF3)") (class "Default")
      (node (ref "U1") (pin "F3") (pinfunction "DQ27_F3") (pintype "passive"))
    )
    (net (code "109") (name "unconnected-(U1B-GPIO45-PadF2)") (class "Default")
      (node (ref "U1") (pin "F2") (pinfunction "GPIO45_F2") (pintype "passive"))
    )
    (net (code "110") (name "unconnected-(U1C-DQ28-PadF5)") (class "Default")
      (node (ref "U1") (pin "F5") (pinfunction "DQ28_F5") (pintype "passive"))
    )
    (net (code "111") (name "unconnected-(U1C-DQ29-PadE1)") (class "Default")
      (node (ref "U1") (pin "E1") (pinfunction "DQ29_E1") (pintype "passive"))
    )
    (net (code "112") (name "unconnected-(U1C-DQ30-PadE5)") (class "Default")
      (node (ref "U1") (pin "E5") (pinfunction "DQ30_E5") (pintype "passive"))
    )
    (net (code "113") (name "unconnected-(U1C-DQ31-PadE4)") (class "Default")
      (node (ref "U1") (pin "E4") (pinfunction "DQ31_E4") (pintype "passive"))
    )
    (net (code "114") (name "unconnected-(U1C-I2S-CLK-PadD1)") (class "Default")
      (node (ref "U1") (pin "D1") (pinfunction "I2S-CLK_D1") (pintype "passive"))
    )
    (net (code "115") (name "unconnected-(U1C-I2S-MCLK-PadC4)") (class "Default")
      (node (ref "U1") (pin "C4") (pinfunction "I2S-MCLK_C4") (pintype "passive"))
    )
    (net (code "116") (name "unconnected-(U1C-I2S-SD-PadD2)") (class "Default")
      (node (ref "U1") (pin "D2") (pinfunction "I2S-SD_D2") (pintype "passive"))
    )
    (net (code "117") (name "unconnected-(U1C-I2S-WS-PadD3)") (class "Default")
      (node (ref "U1") (pin "D3") (pinfunction "I2S-WS_D3") (pintype "passive"))
    )
    (net (code "118") (name "unconnected-(U1E-CLKIN-PadD7)") (class "Default")
      (node (ref "U1") (pin "D7") (pinfunction "CLKIN_D7") (pintype "passive"))
    )
    (net (code "119") (name "unconnected-(U1F-TCK-PadF6)") (class "Default")
      (node (ref "U1") (pin "F6") (pinfunction "TCK_F6") (pintype "passive"))
    )
    (net (code "120") (name "unconnected-(U1F-TDI-PadE7)") (class "Default")
      (node (ref "U1") (pin "E7") (pinfunction "TDI_E7") (pintype "passive"))
    )
    (net (code "121") (name "unconnected-(U1F-TDO-PadC10)") (class "Default")
      (node (ref "U1") (pin "C10") (pinfunction "TDO_C10") (pintype "passive"))
    )
    (net (code "122") (name "unconnected-(U1F-TMS-PadE8)") (class "Default")
      (node (ref "U1") (pin "E8") (pinfunction "TMS_E8") (pintype "passive"))
    )
    (net (code "123") (name "unconnected-(U1F-TRST_N-PadB11)") (class "Default")
      (node (ref "U1") (pin "B11") (pinfunction "TRST_N_B11") (pintype "passive"))
    )
    (net (code "124") (name "unconnected-(U1H-I2C-GPIO60_CHARGER-DETECT-PadD11)") (class "Default")
      (node (ref "U1") (pin "D11") (pinfunction "I2C-GPIO60_CHARGER-DETECT_D11") (pintype "passive+no_connect"))
    )
    (net (code "125") (name "unconnected-(U2-DU1-Pad1)") (class "Default")
      (node (ref "U2") (pin "1") (pinfunction "DU1_1") (pintype "passive"))
    )
    (net (code "126") (name "unconnected-(U2-DU2-Pad2)") (class "Default")
      (node (ref "U2") (pin "2") (pinfunction "DU2_2") (pintype "passive"))
    )
    (net (code "127") (name "unconnected-(U2-E2-Pad3)") (class "Default")
      (node (ref "U2") (pin "3") (pinfunction "E2_3") (pintype "passive"))
    )
    (net (code "128") (name "unconnected-(U2-~{WC}-Pad7)") (class "Default")
      (node (ref "U2") (pin "7") (pinfunction "~{WC}_7") (pintype "passive"))
    )
    (net (code "129") (name "unconnected-(U3-NC-Pad1)") (class "Default")
      (node (ref "U3") (pin "1") (pinfunction "NC_1") (pintype "passive"))
    )
    (net (code "130") (name "unconnected-(U3-NC-Pad2)") (class "Default")
      (node (ref "U3") (pin "2") (pinfunction "NC_2") (pintype "passive"))
    )
    (net (code "131") (name "unconnected-(U3-NC-Pad3)") (class "Default")
      (node (ref "U3") (pin "3") (pinfunction "NC_3") (pintype "passive"))
    )
    (net (code "132") (name "unconnected-(U3-NC-Pad7)") (class "Default")
      (node (ref "U3") (pin "7") (pinfunction "NC_7") (pintype "passive"))
    )
    (net (code "133") (name "unconnected-(U7-FBC-Pad3)") (class "Default")
      (node (ref "U7") (pin "3") (pinfunction "FBC_3") (pintype "passive"))
    )
  )
)
